# input.net
KiCad netlist of a schematic drawn in Altium Designer
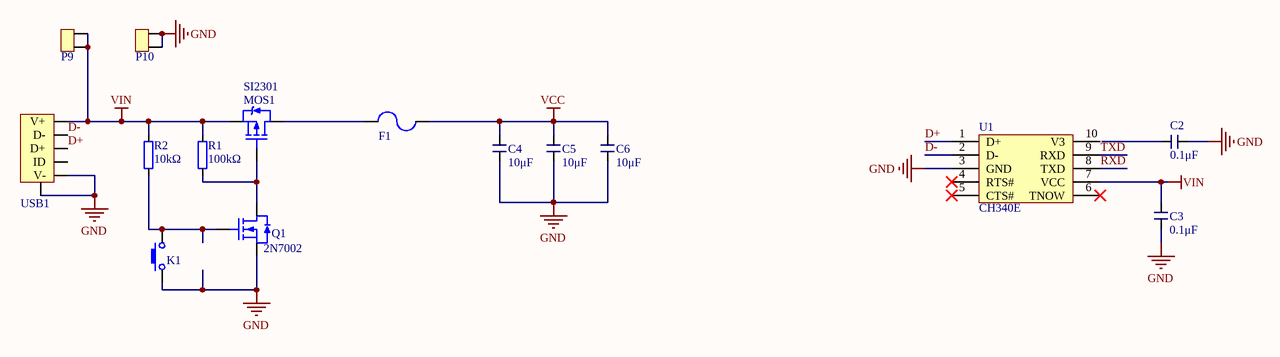
[diagram p0: input.SchDoc]

(export (version "E")
  (design (tool "Eeschema 10.0.6"))
  (components
    (comp (ref "C2") (value "0.1μF") (footprint "C_0603") (libsource (lib "节能库") (part "C_0603")))
    (comp (ref "C3") (value "0.1μF") (footprint "C_0603") (libsource (lib "节能库") (part "C_0603")))
    (comp (ref "C4") (value "10μF") (footprint "C_0805") (libsource (lib "节能库") (part "C_0805")))
    (comp (ref "C5") (value "10μF") (footprint "C_0805") (libsource (lib "节能库") (part "C_0805")))
    (comp (ref "C6") (value "10μF") (footprint "C_0805") (libsource (lib "节能库") (part "C_0805")))
    (comp (ref "F1") (value "A") (footprint "F_1812") (libsource (lib "节能库") (part "FUSE_1812")))
    (comp (ref "K1")
      (value "TACT SWITCH_2_SMD")
      (footprint "TACT SWITCH_2_SMD")
      (libsource (lib "节能库") (part "TACT SWITCH_2_SMD"))
    )
    (comp (ref "MOS1") (value "SI2301") (footprint "SOT_23_3") (libsource (lib "节能库") (part "SI2301")))
    (comp (ref "P9") (value "PIN2") (footprint "PIN_2") (libsource (lib "节能库") (part "PIN2")))
    (comp (ref "P10") (value "PIN2") (footprint "PIN_2") (libsource (lib "节能库") (part "PIN2")))
    (comp (ref "Q1") (value "2N7002") (footprint "SOT_23_3") (libsource (lib "节能库") (part "2N7002")))
    (comp (ref "R1") (value "100kΩ") (footprint "R_0603") (libsource (lib "节能库") (part "R_0603")))
    (comp (ref "R2") (value "10kΩ") (footprint "R_0603") (libsource (lib "节能库") (part "R_0603")))
    (comp (ref "U1") (value "CH340E") (footprint "MSOP_10") (libsource (lib "节能库") (part "CH340E")))
    (comp (ref "USB1")
      (value "MICRO USB B")
      (footprint "MICRO USB B")
      (libsource (lib "节能库") (part "MICRO USB B"))
    )
  )
  (nets
    (net (code "1") (name "/D+") (class "Default")
      (node (ref "U1") (pin "1") (pinfunction "D+_1") (pintype "passive"))
      (node (ref "USB1") (pin "3") (pinfunction "D+_3") (pintype "passive"))
    )
    (net (code "2") (name "/D-") (class "Default")
      (node (ref "U1") (pin "2") (pinfunction "D-_2") (pintype "passive"))
      (node (ref "USB1") (pin "2") (pinfunction "D-_2") (pintype "passive"))
    )
    (net (code "3") (name "/RXD") (class "Default")
      (node (ref "U1") (pin "8") (pinfunction "TXD_8") (pintype "passive"))
    )
    (net (code "4") (name "/TXD") (class "Default")
      (node (ref "U1") (pin "9") (pinfunction "RXD_9") (pintype "passive"))
    )
    (net (code "5") (name "GND") (class "Default")
      (node (ref "C2") (pin "1") (pinfunction "1_1") (pintype "passive"))
      (node (ref "C3") (pin "1") (pinfunction "1_1") (pintype "passive"))
      (node (ref "C4") (pin "2") (pinfunction "2_2") (pintype "passive"))
      (node (ref "C5") (pin "2") (pinfunction "2_2") (pintype "passive"))
      (node (ref "C6") (pin "2") (pinfunction "2_2") (pintype "passive"))
      (node (ref "K1") (pin "1") (pinfunction "1_1") (pintype "passive"))
      (node (ref "P10") (pin "1") (pinfunction "1_1") (pintype "passive"))
      (node (ref "P10") (pin "2") (pinfunction "2_2") (pintype "passive"))
      (node (ref "Q1") (pin "2") (pinfunction "S_2") (pintype "passive"))
      (node (ref "U1") (pin "3") (pinfunction "GND_3") (pintype "passive"))
      (node (ref "USB1") (pin "0") (pinfunction "GND_0") (pintype "passive"))
      (node (ref "USB1") (pin "5") (pinfunction "V-_5") (pintype "passive"))
    )
    (net (code "6") (name "Net-(MOS1-D)") (class "Default")
      (node (ref "F1") (pin "1") (pinfunction "1_1") (pintype "passive"))
      (node (ref "MOS1") (pin "3") (pinfunction "D_3") (pintype "passive"))
    )
    (net (code "7") (name "Net-(MOS1-G)") (class "Default")
      (node (ref "MOS1") (pin "1") (pinfunction "G_1") (pintype "passive"))
      (node (ref "Q1") (pin "3") (pinfunction "D_3") (pintype "passive"))
      (node (ref "R1") (pin "1") (pintype "passive"))
    )
    (net (code "8") (name "Net-(Q1-G)") (class "Default")
      (node (ref "K1") (pin "2") (pinfunction "2_2") (pintype "passive"))
      (node (ref "Q1") (pin "1") (pinfunction "G_1") (pintype "passive"))
      (node (ref "R2") (pin "1") (pintype "passive"))
    )
    (net (code "9") (name "VCC") (class "Default")
      (node (ref "C4") (pin "1") (pinfunction "1_1") (pintype "passive"))
      (node (ref "C5") (pin "1") (pinfunction "1_1") (pintype "passive"))
      (node (ref "C6") (pin "1") (pinfunction "1_1") (pintype "passive"))
      (node (ref "F1") (pin "2") (pinfunction "2_2") (pintype "passive"))
    )
    (net (code "10") (name "VIN") (class "Default")
      (node (ref "C3") (pin "2") (pinfunction "2_2") (pintype "passive"))
      (node (ref "MOS1") (pin "2") (pinfunction "S_2") (pintype "passive"))
      (node (ref "P9") (pin "1") (pinfunction "1_1") (pintype "passive"))
      (node (ref "P9") (pin "2") (pinfunction "2_2") (pintype "passive"))
      (node (ref "R1") (pin "2") (pintype "passive"))
      (node (ref "R2") (pin "2") (pintype "passive"))
      (node (ref "U1") (pin "7") (pinfunction "VCC_7") (pintype "passive"))
      (node (ref "USB1") (pin "1") (pinfunction "V+_1") (pintype "passive"))
    )
    (net (code "11") (name "unconnected-(C2-Pad2)") (class "Default")
      (node (ref "C2") (pin "2") (pinfunction "2_2") (pintype "passive"))
    )
    (net (code "12") (name "unconnected-(U1-CTS#-Pad5)") (class "Default")
      (node (ref "U1") (pin "5") (pinfunction "CTS#_5") (pintype "passive+no_connect"))
    )
    (net (code "13") (name "unconnected-(U1-RTS#-Pad4)") (class "Default")
      (node (ref "U1") (pin "4") (pinfunction "RTS#_4") (pintype "passive+no_connect"))
    )
    (net (code "14") (name "unconnected-(U1-TNOW-Pad6)") (class "Default")
      (node (ref "U1") (pin "6") (pinfunction "TNOW_6") (pintype "passive+no_connect"))
    )
    (net (code "15") (name "unconnected-(U1-V3-Pad10)") (class "Default")
      (node (ref "U1") (pin "10") (pinfunction "V3_10") (pintype "passive"))
    )
    (net (code "16") (name "unconnected-(USB1-ID-Pad4)") (class "Default")
      (node (ref "USB1") (pin "4") (pinfunction "ID_4") (pintype "passive"))
    )
  )
)
